# tenere-controller-rev-D.net
KiCad netlist of a schematic drawn in EAGLE
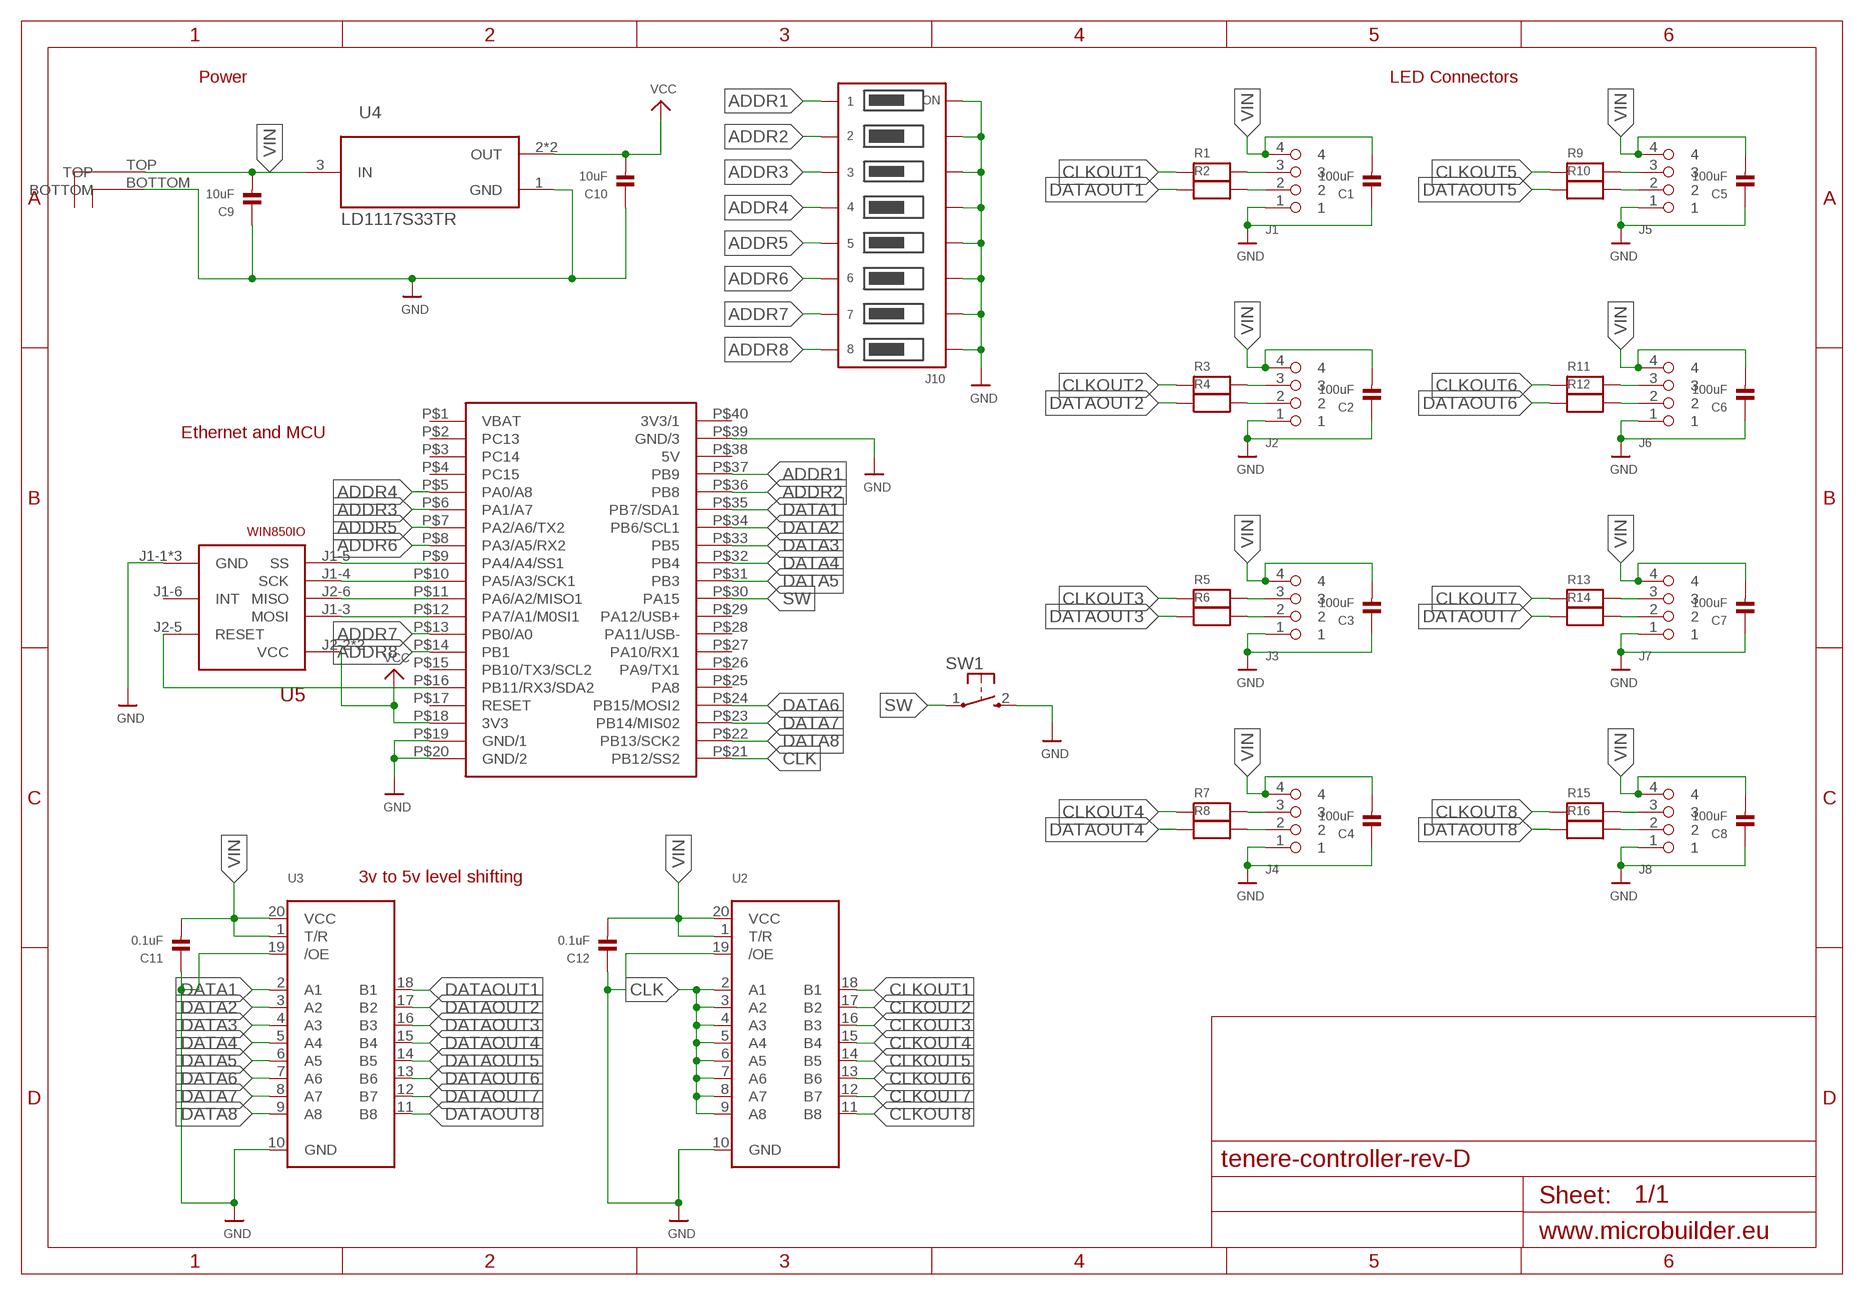
[diagram p0: schematic, sheet 1]

(export (version "E")
  (design (tool "Eeschema 10.0.6"))
  (components
    (comp (ref "C1")
      (value "100uF")
      (footprint "eagle-import:1206")
      (libsource (lib "eagle-import") (part "CAP_CERAMIC1206"))
    )
    (comp (ref "C2")
      (value "100uF")
      (footprint "eagle-import:1206")
      (libsource (lib "eagle-import") (part "CAP_CERAMIC1206"))
    )
    (comp (ref "C3")
      (value "100uF")
      (footprint "eagle-import:1206")
      (libsource (lib "eagle-import") (part "CAP_CERAMIC1206"))
    )
    (comp (ref "C4")
      (value "100uF")
      (footprint "eagle-import:1206")
      (libsource (lib "eagle-import") (part "CAP_CERAMIC1206"))
    )
    (comp (ref "C5")
      (value "100uF")
      (footprint "eagle-import:1206")
      (libsource (lib "eagle-import") (part "CAP_CERAMIC1206"))
    )
    (comp (ref "C6")
      (value "100uF")
      (footprint "eagle-import:1206")
      (libsource (lib "eagle-import") (part "CAP_CERAMIC1206"))
    )
    (comp (ref "C7")
      (value "100uF")
      (footprint "eagle-import:1206")
      (libsource (lib "eagle-import") (part "CAP_CERAMIC1206"))
    )
    (comp (ref "C8")
      (value "100uF")
      (footprint "eagle-import:1206")
      (libsource (lib "eagle-import") (part "CAP_CERAMIC1206"))
    )
    (comp (ref "C9")
      (value "10uF")
      (footprint "eagle-import:0603")
      (libsource (lib "eagle-import") (part "CAP_CERAMIC0603"))
    )
    (comp (ref "C10")
      (value "10uF")
      (footprint "eagle-import:0603")
      (libsource (lib "eagle-import") (part "CAP_CERAMIC0603"))
    )
    (comp (ref "C11")
      (value "0.1uF")
      (footprint "eagle-import:0603")
      (libsource (lib "eagle-import") (part "CAP_CERAMIC0603"))
    )
    (comp (ref "C12")
      (value "0.1uF")
      (footprint "eagle-import:0603")
      (libsource (lib "eagle-import") (part "CAP_CERAMIC0603"))
    )
    (comp (ref "J1")
      (value "MICROFIT3")
      (footprint "eagle-import:43650-0400")
      (libsource (lib "eagle-import") (part "MICROFIT3"))
    )
    (comp (ref "J2")
      (value "MICROFIT3")
      (footprint "eagle-import:43650-0400")
      (libsource (lib "eagle-import") (part "MICROFIT3"))
    )
    (comp (ref "J3")
      (value "MICROFIT3")
      (footprint "eagle-import:43650-0400")
      (libsource (lib "eagle-import") (part "MICROFIT3"))
    )
    (comp (ref "J4")
      (value "MICROFIT3")
      (footprint "eagle-import:43650-0400")
      (libsource (lib "eagle-import") (part "MICROFIT3"))
    )
    (comp (ref "J5")
      (value "MICROFIT3")
      (footprint "eagle-import:43650-0400")
      (libsource (lib "eagle-import") (part "MICROFIT3"))
    )
    (comp (ref "J6")
      (value "MICROFIT3")
      (footprint "eagle-import:43650-0400")
      (libsource (lib "eagle-import") (part "MICROFIT3"))
    )
    (comp (ref "J7")
      (value "MICROFIT3")
      (footprint "eagle-import:43650-0400")
      (libsource (lib "eagle-import") (part "MICROFIT3"))
    )
    (comp (ref "J8")
      (value "MICROFIT3")
      (footprint "eagle-import:43650-0400")
      (libsource (lib "eagle-import") (part "MICROFIT3"))
    )
    (comp (ref "J9")
      (value "POWERPOLE-2V")
      (footprint "eagle-import:POWERPOLE_STACKED")
      (libsource (lib "eagle-import") (part "POWERPOLE-2V"))
    )
    (comp (ref "J10")
      (value "DIP-SWITCH-8PIN")
      (footprint "eagle-import:BPA08B")
      (libsource (lib "eagle-import") (part "DIP-SWITCH-8PIN"))
    )
    (comp (ref "R1")
      (value "RESISTOR0603")
      (footprint "eagle-import:0603")
      (libsource (lib "eagle-import") (part "RESISTOR0603"))
    )
    (comp (ref "R2")
      (value "RESISTOR0603")
      (footprint "eagle-import:0603")
      (libsource (lib "eagle-import") (part "RESISTOR0603"))
    )
    (comp (ref "R3")
      (value "RESISTOR0603")
      (footprint "eagle-import:0603")
      (libsource (lib "eagle-import") (part "RESISTOR0603"))
    )
    (comp (ref "R4")
      (value "RESISTOR0603")
      (footprint "eagle-import:0603")
      (libsource (lib "eagle-import") (part "RESISTOR0603"))
    )
    (comp (ref "R5")
      (value "RESISTOR0603")
      (footprint "eagle-import:0603")
      (libsource (lib "eagle-import") (part "RESISTOR0603"))
    )
    (comp (ref "R6")
      (value "RESISTOR0603")
      (footprint "eagle-import:0603")
      (libsource (lib "eagle-import") (part "RESISTOR0603"))
    )
    (comp (ref "R7")
      (value "RESISTOR0603")
      (footprint "eagle-import:0603")
      (libsource (lib "eagle-import") (part "RESISTOR0603"))
    )
    (comp (ref "R8")
      (value "RESISTOR0603")
      (footprint "eagle-import:0603")
      (libsource (lib "eagle-import") (part "RESISTOR0603"))
    )
    (comp (ref "R9")
      (value "RESISTOR0603")
      (footprint "eagle-import:0603")
      (libsource (lib "eagle-import") (part "RESISTOR0603"))
    )
    (comp (ref "R10")
      (value "RESISTOR0603")
      (footprint "eagle-import:0603")
      (libsource (lib "eagle-import") (part "RESISTOR0603"))
    )
    (comp (ref "R11")
      (value "RESISTOR0603")
      (footprint "eagle-import:0603")
      (libsource (lib "eagle-import") (part "RESISTOR0603"))
    )
    (comp (ref "R12")
      (value "RESISTOR0603")
      (footprint "eagle-import:0603")
      (libsource (lib "eagle-import") (part "RESISTOR0603"))
    )
    (comp (ref "R13")
      (value "RESISTOR0603")
      (footprint "eagle-import:0603")
      (libsource (lib "eagle-import") (part "RESISTOR0603"))
    )
    (comp (ref "R14")
      (value "RESISTOR0603")
      (footprint "eagle-import:0603")
      (libsource (lib "eagle-import") (part "RESISTOR0603"))
    )
    (comp (ref "R15")
      (value "RESISTOR0603")
      (footprint "eagle-import:0603")
      (libsource (lib "eagle-import") (part "RESISTOR0603"))
    )
    (comp (ref "R16")
      (value "RESISTOR0603")
      (footprint "eagle-import:0603")
      (libsource (lib "eagle-import") (part "RESISTOR0603"))
    )
    (comp (ref "SW1")
      (value "TACTILE-SWITCH-1825027")
      (footprint "eagle-import:1825027")
      (libsource (lib "eagle-import") (part "TACTILE-SWITCH-1825027"))
    )
    (comp (ref "U1")
      (value "BLUEPILL")
      (footprint "eagle-import:40-DIP-BLUE-PIL")
      (libsource (lib "eagle-import") (part "BLUEPILL"))
    )
    (comp (ref "U2")
      (value "74LCX245")
      (footprint "eagle-import:TSSOP20")
      (libsource (lib "eagle-import") (part "74LCX245"))
    )
    (comp (ref "U3")
      (value "74LCX245")
      (footprint "eagle-import:TSSOP20")
      (libsource (lib "eagle-import") (part "74LCX245"))
    )
    (comp (ref "U4")
      (value "LD1117S33TR")
      (footprint "eagle-import:LD1117S33TR_SOT230P700X180-4N")
      (fields (field (name "MANUFACTURER") "ST Microelectronics"))
      (libsource (lib "eagle-import") (part "LD1117S33TR"))
    )
    (comp (ref "U5")
      (value "WIN850IO")
      (footprint "eagle-import:WIZ850IO")
      (libsource (lib "eagle-import") (part "WIN850IO"))
    )
  )
  (nets
    (net (code "1") (name "ADDR1") (class "Default")
      (node (ref "J10") (pin "1'") (pinfunction "1B_1'") (pintype "bidirectional"))
      (node (ref "U1") (pin "P$37") (pinfunction "PB9_P$37") (pintype "bidirectional"))
    )
    (net (code "2") (name "ADDR2") (class "Default")
      (node (ref "J10") (pin "2'") (pinfunction "2B_2'") (pintype "bidirectional"))
      (node (ref "U1") (pin "P$36") (pinfunction "PB8_P$36") (pintype "bidirectional"))
    )
    (net (code "3") (name "ADDR3") (class "Default")
      (node (ref "J10") (pin "3'") (pinfunction "3B_3'") (pintype "bidirectional"))
      (node (ref "U1") (pin "P$6") (pinfunction "PA1/A7_P$6") (pintype "bidirectional"))
    )
    (net (code "4") (name "ADDR4") (class "Default")
      (node (ref "J10") (pin "4'") (pinfunction "4B_4'") (pintype "bidirectional"))
      (node (ref "U1") (pin "P$5") (pinfunction "PA0/A8_P$5") (pintype "bidirectional"))
    )
    (net (code "5") (name "ADDR5") (class "Default")
      (node (ref "J10") (pin "5'") (pinfunction "5B_5'") (pintype "bidirectional"))
      (node (ref "U1") (pin "P$7") (pinfunction "PA2/A6/TX2_P$7") (pintype "bidirectional"))
    )
    (net (code "6") (name "ADDR6") (class "Default")
      (node (ref "J10") (pin "6'") (pinfunction "6B_6'") (pintype "bidirectional"))
      (node (ref "U1") (pin "P$8") (pinfunction "PA3/A5/RX2_P$8") (pintype "bidirectional"))
    )
    (net (code "7") (name "ADDR7") (class "Default")
      (node (ref "J10") (pin "7'") (pinfunction "7B_7'") (pintype "bidirectional"))
      (node (ref "U1") (pin "P$13") (pinfunction "PB0/A0_P$13") (pintype "bidirectional"))
    )
    (net (code "8") (name "ADDR8") (class "Default")
      (node (ref "J10") (pin "8'") (pinfunction "8B_8'") (pintype "bidirectional"))
      (node (ref "U1") (pin "P$14") (pinfunction "PB1_P$14") (pintype "bidirectional"))
    )
    (net (code "9") (name "CLK") (class "Default")
      (node (ref "U1") (pin "P$21") (pinfunction "PB12/SS2_P$21") (pintype "bidirectional"))
      (node (ref "U2") (pin "2") (pinfunction "A1_2") (pintype "bidirectional"))
      (node (ref "U2") (pin "3") (pinfunction "A2_3") (pintype "bidirectional"))
      (node (ref "U2") (pin "4") (pinfunction "A3_4") (pintype "bidirectional"))
      (node (ref "U2") (pin "5") (pinfunction "A4_5") (pintype "bidirectional"))
      (node (ref "U2") (pin "6") (pinfunction "A5_6") (pintype "bidirectional"))
      (node (ref "U2") (pin "7") (pinfunction "A6_7") (pintype "bidirectional"))
      (node (ref "U2") (pin "8") (pinfunction "A7_8") (pintype "bidirectional"))
      (node (ref "U2") (pin "9") (pinfunction "A8_9") (pintype "bidirectional"))
    )
    (net (code "10") (name "CLKOUT1") (class "Default")
      (node (ref "R1") (pin "1") (pinfunction "1_1") (pintype "passive"))
      (node (ref "U2") (pin "18") (pinfunction "B1_18") (pintype "bidirectional"))
    )
    (net (code "11") (name "CLKOUT2") (class "Default")
      (node (ref "R3") (pin "1") (pinfunction "1_1") (pintype "passive"))
      (node (ref "U2") (pin "17") (pinfunction "B2_17") (pintype "bidirectional"))
    )
    (net (code "12") (name "CLKOUT3") (class "Default")
      (node (ref "R5") (pin "1") (pinfunction "1_1") (pintype "passive"))
      (node (ref "U2") (pin "16") (pinfunction "B3_16") (pintype "bidirectional"))
    )
    (net (code "13") (name "CLKOUT4") (class "Default")
      (node (ref "R7") (pin "1") (pinfunction "1_1") (pintype "passive"))
      (node (ref "U2") (pin "15") (pinfunction "B4_15") (pintype "bidirectional"))
    )
    (net (code "14") (name "CLKOUT5") (class "Default")
      (node (ref "R9") (pin "1") (pinfunction "1_1") (pintype "passive"))
      (node (ref "U2") (pin "14") (pinfunction "B5_14") (pintype "bidirectional"))
    )
    (net (code "15") (name "CLKOUT6") (class "Default")
      (node (ref "R11") (pin "1") (pinfunction "1_1") (pintype "passive"))
      (node (ref "U2") (pin "13") (pinfunction "B6_13") (pintype "bidirectional"))
    )
    (net (code "16") (name "CLKOUT7") (class "Default")
      (node (ref "R13") (pin "1") (pinfunction "1_1") (pintype "passive"))
      (node (ref "U2") (pin "12") (pinfunction "B7_12") (pintype "bidirectional"))
    )
    (net (code "17") (name "CLKOUT8") (class "Default")
      (node (ref "R15") (pin "1") (pinfunction "1_1") (pintype "passive"))
      (node (ref "U2") (pin "11") (pinfunction "B8_11") (pintype "bidirectional"))
    )
    (net (code "18") (name "DATA1") (class "Default")
      (node (ref "U1") (pin "P$35") (pinfunction "PB7/SDA1_P$35") (pintype "bidirectional"))
      (node (ref "U3") (pin "2") (pinfunction "A1_2") (pintype "bidirectional"))
    )
    (net (code "19") (name "DATA2") (class "Default")
      (node (ref "U1") (pin "P$34") (pinfunction "PB6/SCL1_P$34") (pintype "bidirectional"))
      (node (ref "U3") (pin "3") (pinfunction "A2_3") (pintype "bidirectional"))
    )
    (net (code "20") (name "DATA3") (class "Default")
      (node (ref "U1") (pin "P$33") (pinfunction "PB5_P$33") (pintype "bidirectional"))
      (node (ref "U3") (pin "4") (pinfunction "A3_4") (pintype "bidirectional"))
    )
    (net (code "21") (name "DATA4") (class "Default")
      (node (ref "U1") (pin "P$32") (pinfunction "PB4_P$32") (pintype "bidirectional"))
      (node (ref "U3") (pin "5") (pinfunction "A4_5") (pintype "bidirectional"))
    )
    (net (code "22") (name "DATA5") (class "Default")
      (node (ref "U1") (pin "P$31") (pinfunction "PB3_P$31") (pintype "bidirectional"))
      (node (ref "U3") (pin "6") (pinfunction "A5_6") (pintype "bidirectional"))
    )
    (net (code "23") (name "DATA6") (class "Default")
      (node (ref "U1") (pin "P$24") (pinfunction "PB15/MOSI2_P$24") (pintype "bidirectional"))
      (node (ref "U3") (pin "7") (pinfunction "A6_7") (pintype "bidirectional"))
    )
    (net (code "24") (name "DATA7") (class "Default")
      (node (ref "U1") (pin "P$23") (pinfunction "PB14/MIS02_P$23") (pintype "bidirectional"))
      (node (ref "U3") (pin "8") (pinfunction "A7_8") (pintype "bidirectional"))
    )
    (net (code "25") (name "DATA8") (class "Default")
      (node (ref "U1") (pin "P$22") (pinfunction "PB13/SCK2_P$22") (pintype "bidirectional"))
      (node (ref "U3") (pin "9") (pinfunction "A8_9") (pintype "bidirectional"))
    )
    (net (code "26") (name "DATAOUT1") (class "Default")
      (node (ref "R2") (pin "1") (pinfunction "1_1") (pintype "passive"))
      (node (ref "U3") (pin "18") (pinfunction "B1_18") (pintype "bidirectional"))
    )
    (net (code "27") (name "DATAOUT2") (class "Default")
      (node (ref "R4") (pin "1") (pinfunction "1_1") (pintype "passive"))
      (node (ref "U3") (pin "17") (pinfunction "B2_17") (pintype "bidirectional"))
    )
    (net (code "28") (name "DATAOUT3") (class "Default")
      (node (ref "R6") (pin "1") (pinfunction "1_1") (pintype "passive"))
      (node (ref "U3") (pin "16") (pinfunction "B3_16") (pintype "bidirectional"))
    )
    (net (code "29") (name "DATAOUT4") (class "Default")
      (node (ref "R8") (pin "1") (pinfunction "1_1") (pintype "passive"))
      (node (ref "U3") (pin "15") (pinfunction "B4_15") (pintype "bidirectional"))
    )
    (net (code "30") (name "DATAOUT5") (class "Default")
      (node (ref "R10") (pin "1") (pinfunction "1_1") (pintype "passive"))
      (node (ref "U3") (pin "14") (pinfunction "B5_14") (pintype "bidirectional"))
    )
    (net (code "31") (name "DATAOUT6") (class "Default")
      (node (ref "R12") (pin "1") (pinfunction "1_1") (pintype "passive"))
      (node (ref "U3") (pin "13") (pinfunction "B6_13") (pintype "bidirectional"))
    )
    (net (code "32") (name "DATAOUT7") (class "Default")
      (node (ref "R14") (pin "1") (pinfunction "1_1") (pintype "passive"))
      (node (ref "U3") (pin "12") (pinfunction "B7_12") (pintype "bidirectional"))
    )
    (net (code "33") (name "DATAOUT8") (class "Default")
      (node (ref "R16") (pin "1") (pinfunction "1_1") (pintype "passive"))
      (node (ref "U3") (pin "11") (pinfunction "B8_11") (pintype "bidirectional"))
    )
    (net (code "34") (name "GND") (class "Default")
      (node (ref "C1") (pin "1") (pinfunction "P$1_1") (pintype "passive"))
      (node (ref "C10") (pin "1") (pinfunction "P$1_1") (pintype "passive"))
      (node (ref "C11") (pin "1") (pinfunction "P$1_1") (pintype "passive"))
      (node (ref "C12") (pin "1") (pinfunction "P$1_1") (pintype "passive"))
      (node (ref "C2") (pin "1") (pinfunction "P$1_1") (pintype "passive"))
      (node (ref "C3") (pin "1") (pinfunction "P$1_1") (pintype "passive"))
      (node (ref "C4") (pin "1") (pinfunction "P$1_1") (pintype "passive"))
      (node (ref "C5") (pin "1") (pinfunction "P$1_1") (pintype "passive"))
      (node (ref "C6") (pin "1") (pinfunction "P$1_1") (pintype "passive"))
      (node (ref "C7") (pin "1") (pinfunction "P$1_1") (pintype "passive"))
      (node (ref "C8") (pin "1") (pinfunction "P$1_1") (pintype "passive"))
      (node (ref "C9") (pin "1") (pinfunction "P$1_1") (pintype "passive"))
      (node (ref "J1") (pin "1") (pinfunction "1_1") (pintype "bidirectional"))
      (node (ref "J10") (pin "1") (pinfunction "1A_1") (pintype "bidirectional"))
      (node (ref "J10") (pin "2") (pinfunction "2A_2") (pintype "bidirectional"))
      (node (ref "J10") (pin "3") (pinfunction "3A_3") (pintype "bidirectional"))
      (node (ref "J10") (pin "4") (pinfunction "4A_4") (pintype "bidirectional"))
      (node (ref "J10") (pin "5") (pinfunction "5A_5") (pintype "bidirectional"))
      (node (ref "J10") (pin "6") (pinfunction "6A_6") (pintype "bidirectional"))
      (node (ref "J10") (pin "7") (pinfunction "7A_7") (pintype "bidirectional"))
      (node (ref "J10") (pin "8") (pinfunction "8A_8") (pintype "bidirectional"))
      (node (ref "J2") (pin "1") (pinfunction "1_1") (pintype "bidirectional"))
      (node (ref "J3") (pin "1") (pinfunction "1_1") (pintype "bidirectional"))
      (node (ref "J4") (pin "1") (pinfunction "1_1") (pintype "bidirectional"))
      (node (ref "J5") (pin "1") (pinfunction "1_1") (pintype "bidirectional"))
      (node (ref "J6") (pin "1") (pinfunction "1_1") (pintype "bidirectional"))
      (node (ref "J7") (pin "1") (pinfunction "1_1") (pintype "bidirectional"))
      (node (ref "J8") (pin "1") (pinfunction "1_1") (pintype "bidirectional"))
      (node (ref "J9") (pin "BOTTOM") (pinfunction "BOTTOM_BOTTOM") (pintype "bidirectional"))
      (node (ref "SW1") (pin "2") (pinfunction "3_2") (pintype "passive"))
      (node (ref "U1") (pin "P$19") (pinfunction "GND/1_P$19") (pintype "bidirectional"))
      (node (ref "U1") (pin "P$20") (pinfunction "GND/2_P$20") (pintype "bidirectional"))
      (node (ref "U1") (pin "P$39") (pinfunction "GND/3_P$39") (pintype "bidirectional"))
      (node (ref "U2") (pin "10") (pinfunction "GND_10") (pintype "bidirectional"))
      (node (ref "U2") (pin "19") (pinfunction "/OE_19") (pintype "bidirectional"))
      (node (ref "U3") (pin "10") (pinfunction "GND_10") (pintype "bidirectional"))
      (node (ref "U3") (pin "19") (pinfunction "/OE_19") (pintype "bidirectional"))
      (node (ref "U4") (pin "1") (pinfunction "GND_1") (pintype "power_in"))
      (node (ref "U5") (pin "J1-1") (pinfunction "GND_J1-1") (pintype "bidirectional"))
      (node (ref "U5") (pin "J1-2") (pinfunction "GND_J1-2") (pintype "bidirectional"))
      (node (ref "U5") (pin "J2-1") (pinfunction "GND_J2-1") (pintype "bidirectional"))
    )
    (net (code "35") (name "Net-(J1-Pad2)") (class "Default")
      (node (ref "J1") (pin "2") (pinfunction "2_2") (pintype "bidirectional"))
      (node (ref "R2") (pin "2") (pinfunction "2_2") (pintype "passive"))
    )
    (net (code "36") (name "Net-(J1-Pad3)") (class "Default")
      (node (ref "J1") (pin "3") (pinfunction "3_3") (pintype "bidirectional"))
      (node (ref "R1") (pin "2") (pinfunction "2_2") (pintype "passive"))
    )
    (net (code "37") (name "Net-(J2-Pad2)") (class "Default")
      (node (ref "J2") (pin "2") (pinfunction "2_2") (pintype "bidirectional"))
      (node (ref "R4") (pin "2") (pinfunction "2_2") (pintype "passive"))
    )
    (net (code "38") (name "Net-(J2-Pad3)") (class "Default")
      (node (ref "J2") (pin "3") (pinfunction "3_3") (pintype "bidirectional"))
      (node (ref "R3") (pin "2") (pinfunction "2_2") (pintype "passive"))
    )
    (net (code "39") (name "Net-(J3-Pad2)") (class "Default")
      (node (ref "J3") (pin "2") (pinfunction "2_2") (pintype "bidirectional"))
      (node (ref "R6") (pin "2") (pinfunction "2_2") (pintype "passive"))
    )
    (net (code "40") (name "Net-(J3-Pad3)") (class "Default")
      (node (ref "J3") (pin "3") (pinfunction "3_3") (pintype "bidirectional"))
      (node (ref "R5") (pin "2") (pinfunction "2_2") (pintype "passive"))
    )
    (net (code "41") (name "Net-(J4-Pad2)") (class "Default")
      (node (ref "J4") (pin "2") (pinfunction "2_2") (pintype "bidirectional"))
      (node (ref "R8") (pin "2") (pinfunction "2_2") (pintype "passive"))
    )
    (net (code "42") (name "Net-(J4-Pad3)") (class "Default")
      (node (ref "J4") (pin "3") (pinfunction "3_3") (pintype "bidirectional"))
      (node (ref "R7") (pin "2") (pinfunction "2_2") (pintype "passive"))
    )
    (net (code "43") (name "Net-(J5-Pad2)") (class "Default")
      (node (ref "J5") (pin "2") (pinfunction "2_2") (pintype "bidirectional"))
      (node (ref "R10") (pin "2") (pinfunction "2_2") (pintype "passive"))
    )
    (net (code "44") (name "Net-(J5-Pad3)") (class "Default")
      (node (ref "J5") (pin "3") (pinfunction "3_3") (pintype "bidirectional"))
      (node (ref "R9") (pin "2") (pinfunction "2_2") (pintype "passive"))
    )
    (net (code "45") (name "Net-(J6-Pad2)") (class "Default")
      (node (ref "J6") (pin "2") (pinfunction "2_2") (pintype "bidirectional"))
      (node (ref "R12") (pin "2") (pinfunction "2_2") (pintype "passive"))
    )
    (net (code "46") (name "Net-(J6-Pad3)") (class "Default")
      (node (ref "J6") (pin "3") (pinfunction "3_3") (pintype "bidirectional"))
      (node (ref "R11") (pin "2") (pinfunction "2_2") (pintype "passive"))
    )
    (net (code "47") (name "Net-(J7-Pad2)") (class "Default")
      (node (ref "J7") (pin "2") (pinfunction "2_2") (pintype "bidirectional"))
      (node (ref "R14") (pin "2") (pinfunction "2_2") (pintype "passive"))
    )
    (net (code "48") (name "Net-(J7-Pad3)") (class "Default")
      (node (ref "J7") (pin "3") (pinfunction "3_3") (pintype "bidirectional"))
      (node (ref "R13") (pin "2") (pinfunction "2_2") (pintype "passive"))
    )
    (net (code "49") (name "Net-(J8-Pad2)") (class "Default")
      (node (ref "J8") (pin "2") (pinfunction "2_2") (pintype "bidirectional"))
      (node (ref "R16") (pin "2") (pinfunction "2_2") (pintype "passive"))
    )
    (net (code "50") (name "Net-(J8-Pad3)") (class "Default")
      (node (ref "J8") (pin "3") (pinfunction "3_3") (pintype "bidirectional"))
      (node (ref "R15") (pin "2") (pinfunction "2_2") (pintype "passive"))
    )
    (net (code "51") (name "Net-(U1-PA4{slash}A4{slash}SS1)") (class "Default")
      (node (ref "U1") (pin "P$9") (pinfunction "PA4/A4/SS1_P$9") (pintype "bidirectional"))
      (node (ref "U5") (pin "J1-5") (pinfunction "SS_J1-5") (pintype "bidirectional"))
    )
    (net (code "52") (name "Net-(U1-PA5{slash}A3{slash}SCK1)") (class "Default")
      (node (ref "U1") (pin "P$10") (pinfunction "PA5/A3/SCK1_P$10") (pintype "bidirectional"))
      (node (ref "U5") (pin "J1-4") (pinfunction "SCK_J1-4") (pintype "bidirectional"))
    )
    (net (code "53") (name "Net-(U1-PA6{slash}A2{slash}MISO1)") (class "Default")
      (node (ref "U1") (pin "P$11") (pinfunction "PA6/A2/MISO1_P$11") (pintype "bidirectional"))
      (node (ref "U5") (pin "J2-6") (pinfunction "MISO_J2-6") (pintype "bidirectional"))
    )
    (net (code "54") (name "Net-(U1-PA7{slash}A1{slash}M0SI1)") (class "Default")
      (node (ref "U1") (pin "P$12") (pinfunction "PA7/A1/M0SI1_P$12") (pintype "bidirectional"))
      (node (ref "U5") (pin "J1-3") (pinfunction "MOSI_J1-3") (pintype "bidirectional"))
    )
    (net (code "55") (name "Net-(U1-PB11{slash}RX3{slash}SDA2)") (class "Default")
      (node (ref "U1") (pin "P$16") (pinfunction "PB11/RX3/SDA2_P$16") (pintype "bidirectional"))
      (node (ref "U5") (pin "J2-5") (pinfunction "RESET_J2-5") (pintype "bidirectional"))
    )
    (net (code "56") (name "SW") (class "Default")
      (node (ref "SW1") (pin "1") (pinfunction "1_1") (pintype "passive"))
      (node (ref "U1") (pin "P$30") (pinfunction "PA15_P$30") (pintype "bidirectional"))
    )
    (net (code "57") (name "VCC") (class "Default")
      (node (ref "C10") (pin "2") (pinfunction "P$2_2") (pintype "passive"))
      (node (ref "U1") (pin "P$18") (pinfunction "3V3_P$18") (pintype "bidirectional"))
      (node (ref "U4") (pin "2") (pinfunction "OUT_2") (pintype "output"))
      (node (ref "U4") (pin "4") (pinfunction "OUT_4") (pintype "output"))
      (node (ref "U5") (pin "J2-2") (pinfunction "VCC_J2-2") (pintype "bidirectional"))
      (node (ref "U5") (pin "J2-3") (pinfunction "VCC_J2-3") (pintype "bidirectional"))
    )
    (net (code "58") (name "VIN") (class "Default")
      (node (ref "C1") (pin "2") (pinfunction "P$2_2") (pintype "passive"))
      (node (ref "C11") (pin "2") (pinfunction "P$2_2") (pintype "passive"))
      (node (ref "C12") (pin "2") (pinfunction "P$2_2") (pintype "passive"))
      (node (ref "C2") (pin "2") (pinfunction "P$2_2") (pintype "passive"))
      (node (ref "C3") (pin "2") (pinfunction "P$2_2") (pintype "passive"))
      (node (ref "C4") (pin "2") (pinfunction "P$2_2") (pintype "passive"))
      (node (ref "C5") (pin "2") (pinfunction "P$2_2") (pintype "passive"))
      (node (ref "C6") (pin "2") (pinfunction "P$2_2") (pintype "passive"))
      (node (ref "C7") (pin "2") (pinfunction "P$2_2") (pintype "passive"))
      (node (ref "C8") (pin "2") (pinfunction "P$2_2") (pintype "passive"))
      (node (ref "C9") (pin "2") (pinfunction "P$2_2") (pintype "passive"))
      (node (ref "J1") (pin "4") (pinfunction "4_4") (pintype "bidirectional"))
      (node (ref "J2") (pin "4") (pinfunction "4_4") (pintype "bidirectional"))
      (node (ref "J3") (pin "4") (pinfunction "4_4") (pintype "bidirectional"))
      (node (ref "J4") (pin "4") (pinfunction "4_4") (pintype "bidirectional"))
      (node (ref "J5") (pin "4") (pinfunction "4_4") (pintype "bidirectional"))
      (node (ref "J6") (pin "4") (pinfunction "4_4") (pintype "bidirectional"))
      (node (ref "J7") (pin "4") (pinfunction "4_4") (pintype "bidirectional"))
      (node (ref "J8") (pin "4") (pinfunction "4_4") (pintype "bidirectional"))
      (node (ref "J9") (pin "TOP") (pinfunction "TOP_TOP") (pintype "bidirectional"))
      (node (ref "U2") (pin "1") (pinfunction "T/R_1") (pintype "bidirectional"))
      (node (ref "U2") (pin "20") (pinfunction "VCC_20") (pintype "bidirectional"))
      (node (ref "U3") (pin "1") (pinfunction "T/R_1") (pintype "bidirectional"))
      (node (ref "U3") (pin "20") (pinfunction "VCC_20") (pintype "bidirectional"))
      (node (ref "U4") (pin "3") (pinfunction "IN_3") (pintype "input"))
    )
    (net (code "59") (name "unconnected-(U1-3V3{slash}1-PadP$40)") (class "Default")
      (node (ref "U1") (pin "P$40") (pinfunction "3V3/1_P$40") (pintype "bidirectional"))
    )
    (net (code "60") (name "unconnected-(U1-5V-PadP$38)") (class "Default")
      (node (ref "U1") (pin "P$38") (pinfunction "5V_P$38") (pintype "bidirectional"))
    )
    (net (code "61") (name "unconnected-(U1-PA8-PadP$25)") (class "Default")
      (node (ref "U1") (pin "P$25") (pinfunction "PA8_P$25") (pintype "bidirectional"))
    )
    (net (code "62") (name "unconnected-(U1-PA9{slash}TX1-PadP$26)") (class "Default")
      (node (ref "U1") (pin "P$26") (pinfunction "PA9/TX1_P$26") (pintype "bidirectional"))
    )
    (net (code "63") (name "unconnected-(U1-PA10{slash}RX1-PadP$27)") (class "Default")
      (node (ref "U1") (pin "P$27") (pinfunction "PA10/RX1_P$27") (pintype "bidirectional"))
    )
    (net (code "64") (name "unconnected-(U1-PA11{slash}USB--PadP$28)") (class "Default")
      (node (ref "U1") (pin "P$28") (pinfunction "PA11/USB-_P$28") (pintype "bidirectional"))
    )
    (net (code "65") (name "unconnected-(U1-PA12{slash}USB+-PadP$29)") (class "Default")
      (node (ref "U1") (pin "P$29") (pinfunction "PA12/USB+_P$29") (pintype "bidirectional"))
    )
    (net (code "66") (name "unconnected-(U1-PB10{slash}TX3{slash}SCL2-PadP$15)") (class "Default")
      (node (ref "U1") (pin "P$15") (pinfunction "PB10/TX3/SCL2_P$15") (pintype "bidirectional"))
    )
    (net (code "67") (name "unconnected-(U1-PC13-PadP$2)") (class "Default")
      (node (ref "U1") (pin "P$2") (pinfunction "PC13_P$2") (pintype "bidirectional"))
    )
    (net (code "68") (name "unconnected-(U1-PC14-PadP$3)") (class "Default")
      (node (ref "U1") (pin "P$3") (pinfunction "PC14_P$3") (pintype "bidirectional"))
    )
    (net (code "69") (name "unconnected-(U1-PC15-PadP$4)") (class "Default")
      (node (ref "U1") (pin "P$4") (pinfunction "PC15_P$4") (pintype "bidirectional"))
    )
    (net (code "70") (name "unconnected-(U1-RESET-PadP$17)") (class "Default")
      (node (ref "U1") (pin "P$17") (pinfunction "RESET_P$17") (pintype "bidirectional"))
    )
    (net (code "71") (name "unconnected-(U1-VBAT-PadP$1)") (class "Default")
      (node (ref "U1") (pin "P$1") (pinfunction "VBAT_P$1") (pintype "bidirectional"))
    )
    (net (code "72") (name "unconnected-(U5-INT-PadJ1-6)") (class "Default")
      (node (ref "U5") (pin "J1-6") (pinfunction "INT_J1-6") (pintype "bidirectional"))
    )
  )
)
